# dedo_rev_1_1.net
KiCad netlist of a schematic drawn in EAGLE
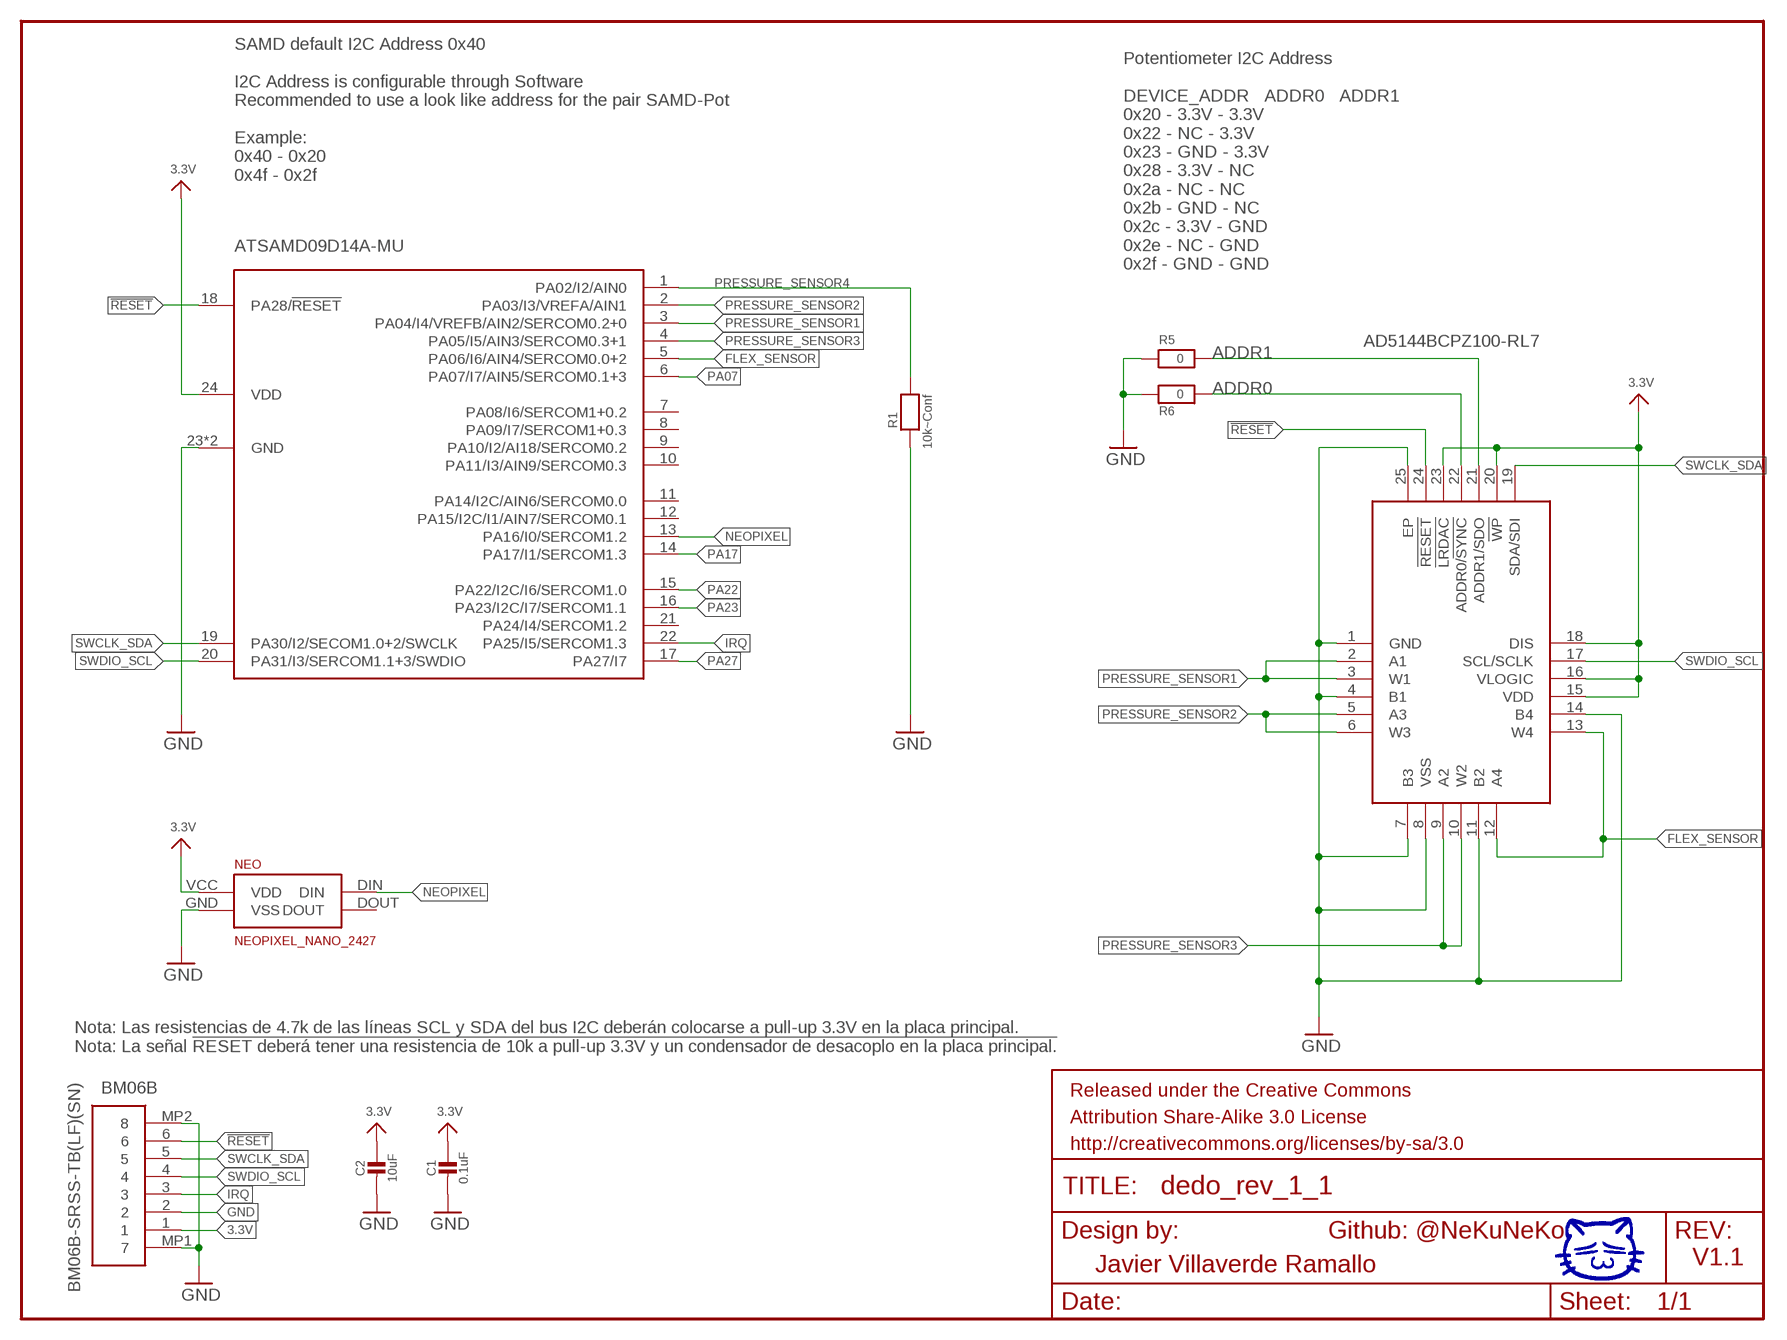
[diagram p0: schematic, sheet 1]

(export (version "E")
  (design (tool "Eeschema 10.0.6"))
  (components
    (comp (ref "AD5144BCPZ100")
      (value "AD5144BCPZ100-RL7")
      (footprint "eagle-import:QFN50P400X400X80-25N")
      (fields (field (name "MOUSER_PART_NUMBER") "584-AD5144BCPZ100-R7"))
      (libsource (lib "eagle-import") (part "AD5144BCPZ100-RL7"))
    )
    (comp (ref "BM06B")
      (value "BM06B-SRSS-TB(LF)(SN)")
      (footprint "eagle-import:BM06BSRSSTBLFSN")
      (fields (field (name "RS_PART_NUMBER") "5468782"))
      (libsource (lib "eagle-import") (part "BM06B-SRSS-TB(LF)(SN)"))
    )
    (comp (ref "C1")
      (value "0.1uF")
      (footprint "eagle-import:0402")
      (libsource (lib "eagle-import") (part "CAP_CERAMIC0402"))
    )
    (comp (ref "C2")
      (value "10uF")
      (footprint "eagle-import:0402")
      (libsource (lib "eagle-import") (part "CAP_CERAMIC0402"))
    )
    (comp (ref "FRAME1")
      (value "FRAME-LETTER")
      (footprint "eagle-import:CREATIVE_COMMONS")
      (libsource (lib "eagle-import") (part "FRAME-LETTER"))
    )
    (comp (ref "FRAME2")
      (value "FRAME-LETTER")
      (footprint "eagle-import:CREATIVE_COMMONS")
      (libsource (lib "eagle-import") (part "FRAME-LETTER"))
    )
    (comp (ref "NEO")
      (value "NEOPIXEL_NANO_2427")
      (footprint "eagle-import:SK6805-2427")
      (libsource (lib "eagle-import") (part "NEOPIXEL_NANO_2427"))
    )
    (comp (ref "R1")
      (value "10k~Conf")
      (footprint "eagle-import:_0402")
      (libsource (lib "eagle-import") (part "RESISTOR_0402"))
    )
    (comp (ref "R5")
      (value "0")
      (footprint "eagle-import:_0402")
      (libsource (lib "eagle-import") (part "RESISTOR_0402"))
    )
    (comp (ref "R6")
      (value "0")
      (footprint "eagle-import:_0402")
      (libsource (lib "eagle-import") (part "RESISTOR_0402"))
    )
    (comp (ref "SAMD09")
      (value "ATSAMD09D14A-MU")
      (footprint "eagle-import:QFN24_4MM")
      (libsource (lib "eagle-import") (part "ATSAMD09D14A-MU"))
    )
  )
  (nets
    (net (code "1") (name "/ADDR0") (class "Default")
      (node (ref "AD5144BCPZ100") (pin "22") (pinfunction "ADDR0/~{SYNC}_22") (pintype "bidirectional"))
      (node (ref "R6") (pin "2") (pinfunction "2_2") (pintype "passive"))
    )
    (net (code "2") (name "/ADDR1") (class "Default")
      (node (ref "AD5144BCPZ100") (pin "21") (pinfunction "ADDR1/SDO_21") (pintype "bidirectional"))
      (node (ref "R5") (pin "2") (pinfunction "2_2") (pintype "passive"))
    )
    (net (code "3") (name "/PRESSURE_SENSOR4") (class "Default")
      (node (ref "R1") (pin "1") (pinfunction "1_1") (pintype "passive"))
      (node (ref "SAMD09") (pin "1") (pinfunction "PA02/I2/AIN0_1") (pintype "bidirectional"))
    )
    (net (code "4") (name "/~{RESET}") (class "Default")
      (node (ref "AD5144BCPZ100") (pin "24") (pinfunction "~{RESET}_24") (pintype "bidirectional"))
      (node (ref "BM06B") (pin "6") (pinfunction "6_6") (pintype "bidirectional"))
      (node (ref "SAMD09") (pin "18") (pinfunction "PA28/~{RESET}_18") (pintype "bidirectional"))
    )
    (net (code "5") (name "3.3V") (class "Default")
      (node (ref "AD5144BCPZ100") (pin "15") (pinfunction "VDD_15") (pintype "bidirectional"))
      (node (ref "AD5144BCPZ100") (pin "16") (pinfunction "VLOGIC_16") (pintype "bidirectional"))
      (node (ref "AD5144BCPZ100") (pin "18") (pinfunction "DIS_18") (pintype "bidirectional"))
      (node (ref "AD5144BCPZ100") (pin "20") (pinfunction "~{WP}_20") (pintype "bidirectional"))
      (node (ref "AD5144BCPZ100") (pin "23") (pinfunction "~{LRDAC}_23") (pintype "bidirectional"))
      (node (ref "BM06B") (pin "1") (pinfunction "1_1") (pintype "bidirectional"))
      (node (ref "C1") (pin "1") (pinfunction "P$1_1") (pintype "passive"))
      (node (ref "C2") (pin "1") (pinfunction "P$1_1") (pintype "passive"))
      (node (ref "NEO") (pin "VCC") (pinfunction "VDD_VCC") (pintype "bidirectional"))
      (node (ref "SAMD09") (pin "24") (pinfunction "VDD_24") (pintype "power_in"))
    )
    (net (code "6") (name "FLEX_SENSOR") (class "Default")
      (node (ref "AD5144BCPZ100") (pin "12") (pinfunction "A4_12") (pintype "bidirectional"))
      (node (ref "AD5144BCPZ100") (pin "13") (pinfunction "W4_13") (pintype "bidirectional"))
      (node (ref "SAMD09") (pin "5") (pinfunction "PA06/I6/AIN4/SERCOM0.0+2_5") (pintype "bidirectional"))
    )
    (net (code "7") (name "GND") (class "Default")
      (node (ref "AD5144BCPZ100") (pin "1") (pinfunction "GND_1") (pintype "bidirectional"))
      (node (ref "AD5144BCPZ100") (pin "11") (pinfunction "B2_11") (pintype "bidirectional"))
      (node (ref "AD5144BCPZ100") (pin "14") (pinfunction "B4_14") (pintype "bidirectional"))
      (node (ref "AD5144BCPZ100") (pin "25") (pinfunction "EP_25") (pintype "bidirectional"))
      (node (ref "AD5144BCPZ100") (pin "4") (pinfunction "B1_4") (pintype "bidirectional"))
      (node (ref "AD5144BCPZ100") (pin "7") (pinfunction "B3_7") (pintype "bidirectional"))
      (node (ref "AD5144BCPZ100") (pin "8") (pinfunction "VSS_8") (pintype "bidirectional"))
      (node (ref "BM06B") (pin "2") (pinfunction "2_2") (pintype "bidirectional"))
      (node (ref "BM06B") (pin "MP1") (pinfunction "7_MP1") (pintype "bidirectional"))
      (node (ref "BM06B") (pin "MP2") (pinfunction "8_MP2") (pintype "bidirectional"))
      (node (ref "C1") (pin "2") (pinfunction "P$2_2") (pintype "passive"))
      (node (ref "C2") (pin "2") (pinfunction "P$2_2") (pintype "passive"))
      (node (ref "NEO") (pin "GND") (pinfunction "VSS_GND") (pintype "bidirectional"))
      (node (ref "R1") (pin "2") (pinfunction "2_2") (pintype "passive"))
      (node (ref "R5") (pin "1") (pinfunction "1_1") (pintype "passive"))
      (node (ref "R6") (pin "1") (pinfunction "1_1") (pintype "passive"))
      (node (ref "SAMD09") (pin "23") (pinfunction "GND_23") (pintype "power_in"))
      (node (ref "SAMD09") (pin "THERM") (pinfunction "GND_THERM") (pintype "power_in"))
    )
    (net (code "8") (name "IRQ") (class "Default")
      (node (ref "BM06B") (pin "3") (pinfunction "3_3") (pintype "bidirectional"))
      (node (ref "SAMD09") (pin "22") (pinfunction "PA25/I5/SERCOM1.3_22") (pintype "bidirectional"))
    )
    (net (code "9") (name "NEOPIXEL") (class "Default")
      (node (ref "NEO") (pin "DIN") (pinfunction "DIN_DIN") (pintype "bidirectional"))
      (node (ref "SAMD09") (pin "13") (pinfunction "PA16/I0/SERCOM1.2_13") (pintype "bidirectional"))
    )
    (net (code "10") (name "PA07") (class "Default")
      (node (ref "SAMD09") (pin "6") (pinfunction "PA07/I7/AIN5/SERCOM0.1+3_6") (pintype "bidirectional"))
    )
    (net (code "11") (name "PA17") (class "Default")
      (node (ref "SAMD09") (pin "14") (pinfunction "PA17/I1/SERCOM1.3_14") (pintype "bidirectional"))
    )
    (net (code "12") (name "PA22") (class "Default")
      (node (ref "SAMD09") (pin "15") (pinfunction "PA22/I2C/I6/SERCOM1.0_15") (pintype "bidirectional"))
    )
    (net (code "13") (name "PA23") (class "Default")
      (node (ref "SAMD09") (pin "16") (pinfunction "PA23/I2C/I7/SERCOM1.1_16") (pintype "bidirectional"))
    )
    (net (code "14") (name "PA27") (class "Default")
      (node (ref "SAMD09") (pin "17") (pinfunction "PA27/I7_17") (pintype "bidirectional"))
    )
    (net (code "15") (name "PRESSURE_SENSOR1") (class "Default")
      (node (ref "AD5144BCPZ100") (pin "2") (pinfunction "A1_2") (pintype "bidirectional"))
      (node (ref "AD5144BCPZ100") (pin "3") (pinfunction "W1_3") (pintype "bidirectional"))
      (node (ref "SAMD09") (pin "3") (pinfunction "PA04/I4/VREFB/AIN2/SERCOM0.2+0_3") (pintype "bidirectional"))
    )
    (net (code "16") (name "PRESSURE_SENSOR2") (class "Default")
      (node (ref "AD5144BCPZ100") (pin "5") (pinfunction "A3_5") (pintype "bidirectional"))
      (node (ref "AD5144BCPZ100") (pin "6") (pinfunction "W3_6") (pintype "bidirectional"))
      (node (ref "SAMD09") (pin "2") (pinfunction "PA03/I3/VREFA/AIN1_2") (pintype "bidirectional"))
    )
    (net (code "17") (name "PRESSURE_SENSOR3") (class "Default")
      (node (ref "AD5144BCPZ100") (pin "10") (pinfunction "W2_10") (pintype "bidirectional"))
      (node (ref "AD5144BCPZ100") (pin "9") (pinfunction "A2_9") (pintype "bidirectional"))
      (node (ref "SAMD09") (pin "4") (pinfunction "PA05/I5/AIN3/SERCOM0.3+1_4") (pintype "bidirectional"))
    )
    (net (code "18") (name "SWCLK_SDA") (class "Default")
      (node (ref "AD5144BCPZ100") (pin "19") (pinfunction "SDA/SDI_19") (pintype "bidirectional"))
      (node (ref "BM06B") (pin "5") (pinfunction "5_5") (pintype "bidirectional"))
      (node (ref "SAMD09") (pin "19") (pinfunction "PA30/I2/SECOM1.0+2/SWCLK_19") (pintype "bidirectional"))
    )
    (net (code "19") (name "SWDIO_SCL") (class "Default")
      (node (ref "AD5144BCPZ100") (pin "17") (pinfunction "SCL/SCLK_17") (pintype "bidirectional"))
      (node (ref "BM06B") (pin "4") (pinfunction "4_4") (pintype "bidirectional"))
      (node (ref "SAMD09") (pin "20") (pinfunction "PA31/I3/SERCOM1.1+3/SWDIO_20") (pintype "bidirectional"))
    )
    (net (code "20") (name "unconnected-(NEO-PadDOUT)") (class "Default")
      (node (ref "NEO") (pin "DOUT") (pinfunction "DOUT_DOUT") (pintype "bidirectional"))
    )
    (net (code "21") (name "unconnected-(SAMD09-PA08{slash}I6{slash}SERCOM1+0.2-Pad7)") (class "Default")
      (node (ref "SAMD09") (pin "7") (pinfunction "PA08/I6/SERCOM1+0.2_7") (pintype "bidirectional"))
    )
    (net (code "22") (name "unconnected-(SAMD09-PA09{slash}I7{slash}SERCOM1+0.3-Pad8)") (class "Default")
      (node (ref "SAMD09") (pin "8") (pinfunction "PA09/I7/SERCOM1+0.3_8") (pintype "bidirectional"))
    )
    (net (code "23") (name "unconnected-(SAMD09-PA10{slash}I2{slash}AI18{slash}SERCOM0.2-Pad9)") (class "Default")
      (node (ref "SAMD09") (pin "9") (pinfunction "PA10/I2/AI18/SERCOM0.2_9") (pintype "bidirectional"))
    )
    (net (code "24") (name "unconnected-(SAMD09-PA11{slash}I3{slash}AIN9{slash}SERCOM0.3-Pad10)") (class "Default")
      (node (ref "SAMD09") (pin "10") (pinfunction "PA11/I3/AIN9/SERCOM0.3_10") (pintype "bidirectional"))
    )
    (net (code "25") (name "unconnected-(SAMD09-PA14{slash}I2C{slash}AIN6{slash}SERCOM0.0-Pad11)") (class "Default")
      (node (ref "SAMD09") (pin "11") (pinfunction "PA14/I2C/AIN6/SERCOM0.0_11") (pintype "bidirectional"))
    )
    (net (code "26") (name "unconnected-(SAMD09-PA15{slash}I2C{slash}I1{slash}AIN7{slash}SERCOM0.1-Pad12)") (class "Default")
      (node (ref "SAMD09") (pin "12") (pinfunction "PA15/I2C/I1/AIN7/SERCOM0.1_12") (pintype "bidirectional"))
    )
    (net (code "27") (name "unconnected-(SAMD09-PA24{slash}I4{slash}SERCOM1.2-Pad21)") (class "Default")
      (node (ref "SAMD09") (pin "21") (pinfunction "PA24/I4/SERCOM1.2_21") (pintype "bidirectional"))
    )
  )
)
